# threshold_control_device_smd.net
KiCad netlist of a schematic drawn in EAGLE
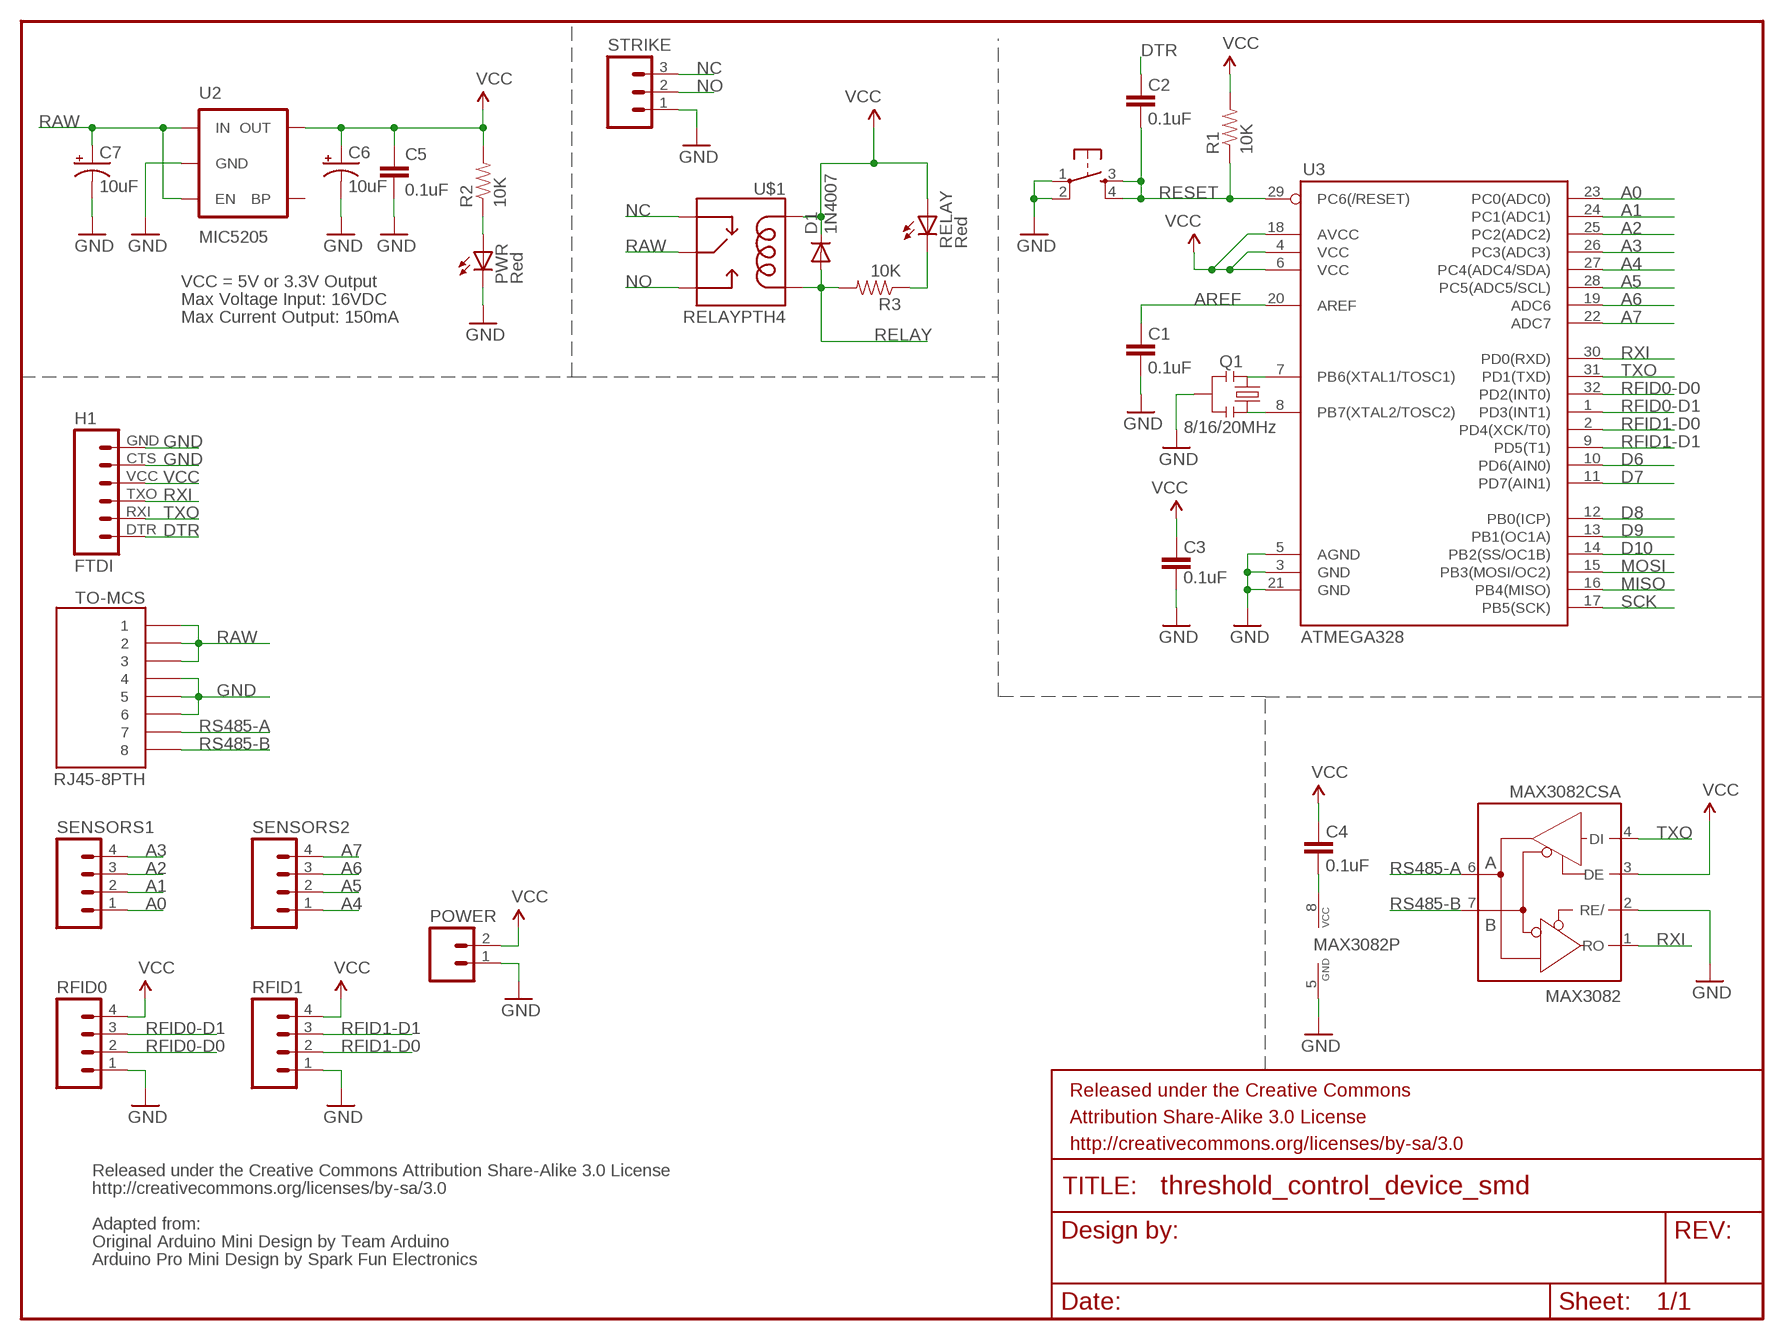
[diagram p0: schematic, sheet 1]

(export (version "E")
  (design (tool "Eeschema 10.0.6"))
  (components
    (comp (ref "C1")
      (value "0.1uF")
      (footprint "eagle-import:0402-CAP")
      (libsource (lib "eagle-import") (part "CAP0402-CAP"))
    )
    (comp (ref "C2")
      (value "0.1uF")
      (footprint "eagle-import:0402-CAP")
      (libsource (lib "eagle-import") (part "CAP0402-CAP"))
    )
    (comp (ref "C3")
      (value "0.1uF")
      (footprint "eagle-import:0402-CAP")
      (libsource (lib "eagle-import") (part "CAP0402-CAP"))
    )
    (comp (ref "C4")
      (value "0.1uF")
      (footprint "eagle-import:0402-CAP")
      (libsource (lib "eagle-import") (part "CAP0402-CAP"))
    )
    (comp (ref "C5")
      (value "0.1uF")
      (footprint "eagle-import:0402-CAP")
      (libsource (lib "eagle-import") (part "CAP0402-CAP"))
    )
    (comp (ref "C6")
      (value "10uF")
      (footprint "eagle-import:EIA3216")
      (libsource (lib "eagle-import") (part "CAP_POL1206"))
    )
    (comp (ref "C7")
      (value "10uF")
      (footprint "eagle-import:EIA3216")
      (libsource (lib "eagle-import") (part "CAP_POL1206"))
    )
    (comp (ref "D1")
      (value "1N4007")
      (footprint "eagle-import:SMA-DIODE")
      (libsource (lib "eagle-import") (part "DIODESMA"))
    )
    (comp (ref "FRAME1")
      (value "FRAME-LETTER")
      (footprint "eagle-import:CREATIVE_COMMONS")
      (libsource (lib "eagle-import") (part "FRAME-LETTER"))
    )
    (comp (ref "H1")
      (value "FTDI")
      (footprint "eagle-import:FTDI_BASIC")
      (libsource (lib "eagle-import") (part "FTDI_BASICPTH"))
    )
    (comp (ref "MAX3082")
      (value "MAX3082CSA")
      (footprint "eagle-import:SO08")
      (fields (field (name "MF") "MAXIM") (field (name "MPN") "MAX481CSA"))
      (libsource (lib "eagle-import") (part "MAX481CSA"))
    )
    (comp (ref "POWER")
      (value "M023.5MM")
      (footprint "eagle-import:SCREWTERMINAL-3.5MM-2")
      (libsource (lib "eagle-import") (part "M023.5MM"))
    )
    (comp (ref "PWR")
      (value "Red")
      (footprint "eagle-import:LED-0603")
      (libsource (lib "eagle-import") (part "LED0603"))
    )
    (comp (ref "Q1")
      (value "8/16/20MHz")
      (footprint "eagle-import:RESONATOR-SMD")
      (libsource (lib "eagle-import") (part "RESONATORSMD"))
    )
    (comp (ref "R1")
      (value "10K")
      (footprint "eagle-import:0402-RES")
      (libsource (lib "eagle-import") (part "RESISTOR0402-RES"))
    )
    (comp (ref "R2")
      (value "10K")
      (footprint "eagle-import:0402-RES")
      (libsource (lib "eagle-import") (part "RESISTOR0402-RES"))
    )
    (comp (ref "R3")
      (value "10K")
      (footprint "eagle-import:0402-RES")
      (libsource (lib "eagle-import") (part "RESISTOR0402-RES"))
    )
    (comp (ref "RELAY")
      (value "Red")
      (footprint "eagle-import:LED-0603")
      (libsource (lib "eagle-import") (part "LED0603"))
    )
    (comp (ref "RESET")
      (value "Reset")
      (footprint "eagle-import:TACTILE_SWITCH_SMD")
      (libsource (lib "eagle-import") (part "TAC_SWITCHSMD"))
    )
    (comp (ref "RFID0")
      (value "M04SCREW")
      (footprint "eagle-import:SCREWTERMINAL-3.5MM-4")
      (libsource (lib "eagle-import") (part "M04SCREW"))
    )
    (comp (ref "RFID1")
      (value "M04SCREW")
      (footprint "eagle-import:SCREWTERMINAL-3.5MM-4")
      (libsource (lib "eagle-import") (part "M04SCREW"))
    )
    (comp (ref "SENSORS1")
      (value "M04SCREW")
      (footprint "eagle-import:SCREWTERMINAL-3.5MM-4")
      (libsource (lib "eagle-import") (part "M04SCREW"))
    )
    (comp (ref "SENSORS2")
      (value "M04SCREW")
      (footprint "eagle-import:SCREWTERMINAL-3.5MM-4")
      (libsource (lib "eagle-import") (part "M04SCREW"))
    )
    (comp (ref "STRIKE")
      (value "M03SCREW")
      (footprint "eagle-import:SCREWTERMINAL-3.5MM-3")
      (libsource (lib "eagle-import") (part "M03SCREW"))
    )
    (comp (ref "TO-MCS")
      (value "RJ45-8PTH")
      (footprint "eagle-import:RJ45-8")
      (libsource (lib "eagle-import") (part "RJ45-8PTH"))
    )
    (comp (ref "U$1")
      (value "RELAYPTH4")
      (footprint "eagle-import:RELAY-JZC")
      (libsource (lib "eagle-import") (part "RELAYPTH4"))
    )
    (comp (ref "U2")
      (value "MIC5205")
      (footprint "eagle-import:SOT23-5")
      (libsource (lib "eagle-import") (part "V_REG_LDOSMD"))
    )
    (comp (ref "U3")
      (value "ATMEGA328")
      (footprint "eagle-import:TQFP32-08")
      (libsource (lib "eagle-import") (part "ATMEGA168"))
    )
  )
  (nets
    (net (code "1") (name "/A0") (class "Default")
      (node (ref "SENSORS1") (pin "1") (pinfunction "1_1") (pintype "passive"))
      (node (ref "U3") (pin "23") (pinfunction "PC0(ADC0)_23") (pintype "bidirectional"))
    )
    (net (code "2") (name "/A1") (class "Default")
      (node (ref "SENSORS1") (pin "2") (pinfunction "2_2") (pintype "passive"))
      (node (ref "U3") (pin "24") (pinfunction "PC1(ADC1)_24") (pintype "bidirectional"))
    )
    (net (code "3") (name "/A2") (class "Default")
      (node (ref "SENSORS1") (pin "3") (pinfunction "3_3") (pintype "passive"))
      (node (ref "U3") (pin "25") (pinfunction "PC2(ADC2)_25") (pintype "bidirectional"))
    )
    (net (code "4") (name "/A3") (class "Default")
      (node (ref "SENSORS1") (pin "4") (pinfunction "4_4") (pintype "passive"))
      (node (ref "U3") (pin "26") (pinfunction "PC3(ADC3)_26") (pintype "bidirectional"))
    )
    (net (code "5") (name "/A4") (class "Default")
      (node (ref "SENSORS2") (pin "1") (pinfunction "1_1") (pintype "passive"))
      (node (ref "U3") (pin "27") (pinfunction "PC4(ADC4/SDA)_27") (pintype "bidirectional"))
    )
    (net (code "6") (name "/A5") (class "Default")
      (node (ref "SENSORS2") (pin "2") (pinfunction "2_2") (pintype "passive"))
      (node (ref "U3") (pin "28") (pinfunction "PC5(ADC5/SCL)_28") (pintype "bidirectional"))
    )
    (net (code "7") (name "/A6") (class "Default")
      (node (ref "SENSORS2") (pin "3") (pinfunction "3_3") (pintype "passive"))
      (node (ref "U3") (pin "19") (pinfunction "ADC6_19") (pintype "bidirectional"))
    )
    (net (code "8") (name "/A7") (class "Default")
      (node (ref "SENSORS2") (pin "4") (pinfunction "4_4") (pintype "passive"))
      (node (ref "U3") (pin "22") (pinfunction "ADC7_22") (pintype "bidirectional"))
    )
    (net (code "9") (name "/AREF") (class "Default")
      (node (ref "C1") (pin "2") (pinfunction "2_2") (pintype "passive"))
      (node (ref "U3") (pin "20") (pinfunction "AREF_20") (pintype "bidirectional"))
    )
    (net (code "10") (name "/D6") (class "Default")
      (node (ref "U3") (pin "10") (pinfunction "PD6(AIN0)_10") (pintype "bidirectional"))
    )
    (net (code "11") (name "/D7") (class "Default")
      (node (ref "U3") (pin "11") (pinfunction "PD7(AIN1)_11") (pintype "bidirectional"))
    )
    (net (code "12") (name "/D8") (class "Default")
      (node (ref "U3") (pin "12") (pinfunction "PB0(ICP)_12") (pintype "bidirectional"))
    )
    (net (code "13") (name "/D9") (class "Default")
      (node (ref "U3") (pin "13") (pinfunction "PB1(OC1A)_13") (pintype "bidirectional"))
    )
    (net (code "14") (name "/D10") (class "Default")
      (node (ref "U3") (pin "14") (pinfunction "PB2(SS/OC1B)_14") (pintype "bidirectional"))
    )
    (net (code "15") (name "/DTR") (class "Default")
      (node (ref "C2") (pin "2") (pinfunction "2_2") (pintype "passive"))
      (node (ref "H1") (pin "DTR") (pinfunction "1_DTR") (pintype "passive"))
    )
    (net (code "16") (name "/MISO") (class "Default")
      (node (ref "U3") (pin "16") (pinfunction "PB4(MISO)_16") (pintype "bidirectional"))
    )
    (net (code "17") (name "/MOSI") (class "Default")
      (node (ref "U3") (pin "15") (pinfunction "PB3(MOSI/OC2)_15") (pintype "bidirectional"))
    )
    (net (code "18") (name "/NC") (class "Default")
      (node (ref "STRIKE") (pin "3") (pinfunction "3_3") (pintype "passive"))
      (node (ref "U$1") (pin "2") (pinfunction "NC_2") (pintype "bidirectional"))
    )
    (net (code "19") (name "/NO") (class "Default")
      (node (ref "STRIKE") (pin "2") (pinfunction "2_2") (pintype "passive"))
      (node (ref "U$1") (pin "3") (pinfunction "NO_3") (pintype "bidirectional"))
    )
    (net (code "20") (name "/RAW") (class "Default")
      (node (ref "C7") (pin "A") (pinfunction "+_A") (pintype "passive"))
      (node (ref "TO-MCS") (pin "1") (pinfunction "1_1") (pintype "bidirectional"))
      (node (ref "TO-MCS") (pin "2") (pinfunction "2_2") (pintype "bidirectional"))
      (node (ref "TO-MCS") (pin "3") (pinfunction "3_3") (pintype "bidirectional"))
      (node (ref "U$1") (pin "4") (pinfunction "MAIN_4") (pintype "bidirectional"))
      (node (ref "U2") (pin "1") (pinfunction "IN_1") (pintype "input"))
      (node (ref "U2") (pin "3") (pinfunction "EN_3") (pintype "input"))
    )
    (net (code "21") (name "/RELAY") (class "Default")
      (node (ref "D1") (pin "A") (pinfunction "A_A") (pintype "passive"))
      (node (ref "R3") (pin "2") (pinfunction "2_2") (pintype "passive"))
      (node (ref "U$1") (pin "1") (pinfunction "COIL2_1") (pintype "bidirectional"))
    )
    (net (code "22") (name "/RESET") (class "Default")
      (node (ref "C2") (pin "1") (pinfunction "1_1") (pintype "passive"))
      (node (ref "R1") (pin "1") (pinfunction "1_1") (pintype "passive"))
      (node (ref "RESET") (pin "3") (pinfunction "3_3") (pintype "passive"))
      (node (ref "RESET") (pin "4") (pinfunction "4_4") (pintype "passive"))
      (node (ref "U3") (pin "29") (pinfunction "PC6(/RESET)_29") (pintype "bidirectional"))
    )
    (net (code "23") (name "/RFID0-D0") (class "Default")
      (node (ref "RFID0") (pin "2") (pinfunction "2_2") (pintype "passive"))
      (node (ref "U3") (pin "32") (pinfunction "PD2(INT0)_32") (pintype "bidirectional"))
    )
    (net (code "24") (name "/RFID0-D1") (class "Default")
      (node (ref "RFID0") (pin "3") (pinfunction "3_3") (pintype "passive"))
      (node (ref "U3") (pin "1") (pinfunction "PD3(INT1)_1") (pintype "bidirectional"))
    )
    (net (code "25") (name "/RFID1-D0") (class "Default")
      (node (ref "RFID1") (pin "2") (pinfunction "2_2") (pintype "passive"))
      (node (ref "U3") (pin "2") (pinfunction "PD4(XCK/T0)_2") (pintype "bidirectional"))
    )
    (net (code "26") (name "/RFID1-D1") (class "Default")
      (node (ref "RFID1") (pin "3") (pinfunction "3_3") (pintype "passive"))
      (node (ref "U3") (pin "9") (pinfunction "PD5(T1)_9") (pintype "bidirectional"))
    )
    (net (code "27") (name "/RS485-A") (class "Default")
      (node (ref "MAX3082") (pin "6") (pinfunction "A_6") (pintype "passive"))
      (node (ref "TO-MCS") (pin "7") (pinfunction "7_7") (pintype "bidirectional"))
    )
    (net (code "28") (name "/RS485-B") (class "Default")
      (node (ref "MAX3082") (pin "7") (pinfunction "B_7") (pintype "passive"))
      (node (ref "TO-MCS") (pin "8") (pinfunction "8_8") (pintype "bidirectional"))
    )
    (net (code "29") (name "/RXI") (class "Default")
      (node (ref "H1") (pin "TXO") (pinfunction "3_TXO") (pintype "passive"))
      (node (ref "MAX3082") (pin "1") (pinfunction "RO_1") (pintype "output"))
      (node (ref "U3") (pin "30") (pinfunction "PD0(RXD)_30") (pintype "bidirectional"))
    )
    (net (code "30") (name "/SCK") (class "Default")
      (node (ref "U3") (pin "17") (pinfunction "PB5(SCK)_17") (pintype "bidirectional"))
    )
    (net (code "31") (name "/TXO") (class "Default")
      (node (ref "H1") (pin "RXI") (pinfunction "2_RXI") (pintype "passive"))
      (node (ref "MAX3082") (pin "4") (pinfunction "DI_4") (pintype "input"))
      (node (ref "U3") (pin "31") (pinfunction "PD1(TXD)_31") (pintype "bidirectional"))
    )
    (net (code "32") (name "GND") (class "Default")
      (node (ref "C1") (pin "1") (pinfunction "1_1") (pintype "passive"))
      (node (ref "C3") (pin "1") (pinfunction "1_1") (pintype "passive"))
      (node (ref "C5") (pin "2") (pinfunction "2_2") (pintype "passive"))
      (node (ref "C6") (pin "C") (pinfunction "-_C") (pintype "passive"))
      (node (ref "C7") (pin "C") (pinfunction "-_C") (pintype "passive"))
      (node (ref "H1") (pin "CTS") (pinfunction "5_CTS") (pintype "passive"))
      (node (ref "H1") (pin "GND") (pinfunction "6_GND") (pintype "passive"))
      (node (ref "MAX3082") (pin "2") (pinfunction "RE/_2") (pintype "input"))
      (node (ref "MAX3082") (pin "5") (pinfunction "GND_5") (pintype "power_in"))
      (node (ref "POWER") (pin "1") (pinfunction "1_1") (pintype "passive"))
      (node (ref "PWR") (pin "C") (pinfunction "C_C") (pintype "passive"))
      (node (ref "Q1") (pin "2") (pinfunction "2_2") (pintype "passive"))
      (node (ref "RESET") (pin "1") (pinfunction "1_1") (pintype "passive"))
      (node (ref "RESET") (pin "2") (pinfunction "2_2") (pintype "passive"))
      (node (ref "RFID0") (pin "1") (pinfunction "1_1") (pintype "passive"))
      (node (ref "RFID1") (pin "1") (pinfunction "1_1") (pintype "passive"))
      (node (ref "STRIKE") (pin "1") (pinfunction "1_1") (pintype "passive"))
      (node (ref "TO-MCS") (pin "4") (pinfunction "4_4") (pintype "bidirectional"))
      (node (ref "TO-MCS") (pin "5") (pinfunction "5_5") (pintype "bidirectional"))
      (node (ref "TO-MCS") (pin "6") (pinfunction "6_6") (pintype "bidirectional"))
      (node (ref "U2") (pin "2") (pinfunction "GND_2") (pintype "input"))
      (node (ref "U3") (pin "21") (pinfunction "GND_21") (pintype "bidirectional"))
      (node (ref "U3") (pin "3") (pinfunction "GND_3") (pintype "bidirectional"))
      (node (ref "U3") (pin "5") (pinfunction "AGND_5") (pintype "bidirectional"))
    )
    (net (code "33") (name "Net-(MAX3082B-VCC)") (class "Default")
      (node (ref "C4") (pin "1") (pinfunction "1_1") (pintype "passive"))
      (node (ref "MAX3082") (pin "8") (pinfunction "VCC_8") (pintype "power_in"))
    )
    (net (code "34") (name "Net-(PWR-PadA)") (class "Default")
      (node (ref "PWR") (pin "A") (pinfunction "A_A") (pintype "passive"))
      (node (ref "R2") (pin "1") (pinfunction "1_1") (pintype "passive"))
    )
    (net (code "35") (name "Net-(R3-Pad1)") (class "Default")
      (node (ref "R3") (pin "1") (pinfunction "1_1") (pintype "passive"))
      (node (ref "RELAY") (pin "C") (pinfunction "C_C") (pintype "passive"))
    )
    (net (code "36") (name "Net-(U3-PB6(XTAL1{slash}TOSC1))") (class "Default")
      (node (ref "Q1") (pin "3") (pinfunction "3_3") (pintype "passive"))
      (node (ref "U3") (pin "7") (pinfunction "PB6(XTAL1/TOSC1)_7") (pintype "bidirectional"))
    )
    (net (code "37") (name "Net-(U3-PB7(XTAL2{slash}TOSC2))") (class "Default")
      (node (ref "Q1") (pin "1") (pinfunction "1_1") (pintype "passive"))
      (node (ref "U3") (pin "8") (pinfunction "PB7(XTAL2/TOSC2)_8") (pintype "bidirectional"))
    )
    (net (code "38") (name "VCC") (class "Default")
      (node (ref "C3") (pin "2") (pinfunction "2_2") (pintype "passive"))
      (node (ref "C4") (pin "2") (pinfunction "2_2") (pintype "passive"))
      (node (ref "C5") (pin "1") (pinfunction "1_1") (pintype "passive"))
      (node (ref "C6") (pin "A") (pinfunction "+_A") (pintype "passive"))
      (node (ref "D1") (pin "C") (pinfunction "C_C") (pintype "passive"))
      (node (ref "H1") (pin "VCC") (pinfunction "4_VCC") (pintype "passive"))
      (node (ref "MAX3082") (pin "3") (pinfunction "DE_3") (pintype "input"))
      (node (ref "POWER") (pin "2") (pinfunction "2_2") (pintype "passive"))
      (node (ref "R1") (pin "2") (pinfunction "2_2") (pintype "passive"))
      (node (ref "R2") (pin "2") (pinfunction "2_2") (pintype "passive"))
      (node (ref "RELAY") (pin "A") (pinfunction "A_A") (pintype "passive"))
      (node (ref "RFID0") (pin "4") (pinfunction "4_4") (pintype "passive"))
      (node (ref "RFID1") (pin "4") (pinfunction "4_4") (pintype "passive"))
      (node (ref "U$1") (pin "5") (pinfunction "COIL1_5") (pintype "bidirectional"))
      (node (ref "U2") (pin "5") (pinfunction "OUT_5") (pintype "passive"))
      (node (ref "U3") (pin "18") (pinfunction "AVCC_18") (pintype "bidirectional"))
      (node (ref "U3") (pin "4") (pinfunction "VCC_4") (pintype "bidirectional"))
      (node (ref "U3") (pin "6") (pinfunction "VCC_6") (pintype "bidirectional"))
    )
    (net (code "39") (name "unconnected-(U2-BP-Pad4)") (class "Default")
      (node (ref "U2") (pin "4") (pinfunction "BP_4") (pintype "input"))
    )
  )
)
